# pihat.net
KiCad netlist of a schematic drawn in EAGLE
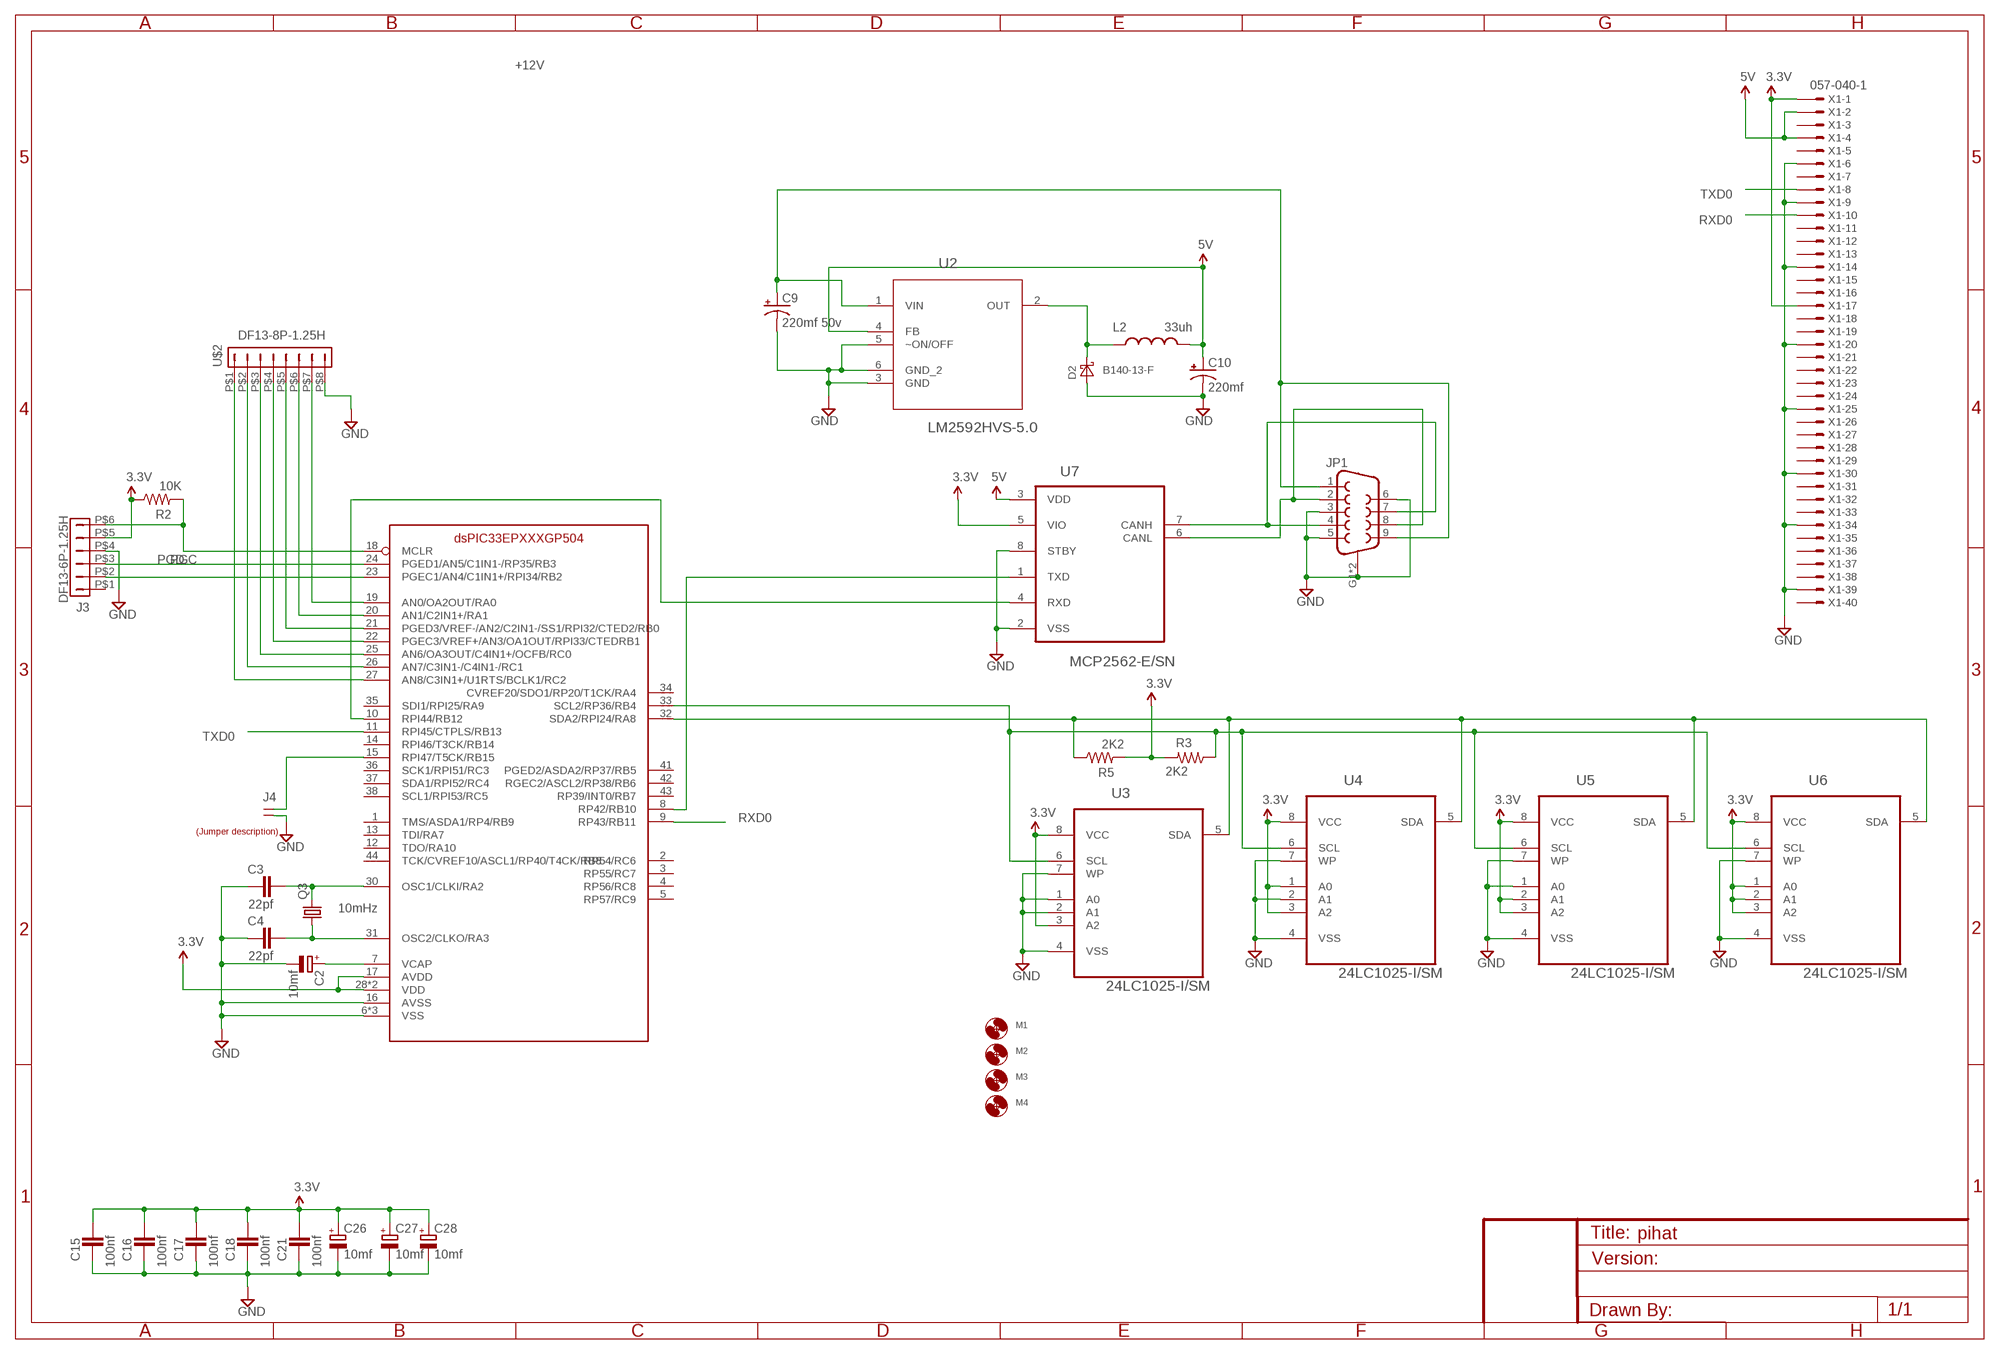
[diagram p0: schematic, sheet 1]

(export (version "E")
  (design (tool "Eeschema 10.0.6"))
  (components
    (comp (ref "C2")
      (value "10mf")
      (footprint "eagle-import:SMC_A")
      (fields (field (name "PARTNO") "T491A106K004AT"))
      (libsource (lib "eagle-import") (part "CAPACITOR_POL-SMC_A"))
    )
    (comp (ref "C3")
      (value "22pf")
      (footprint "eagle-import:C805")
      (fields (field (name "PARTNO") "C0805C220J5GACTU"))
      (libsource (lib "eagle-import") (part "CAPACITOR_NPOL-0805"))
    )
    (comp (ref "C4")
      (value "22pf")
      (footprint "eagle-import:C805")
      (fields (field (name "PARTNO") "C0805C220J5GACTU"))
      (libsource (lib "eagle-import") (part "CAPACITOR_NPOL-0805"))
    )
    (comp (ref "C9")
      (value "220mf 50v")
      (footprint "eagle-import:EIA7343")
      (fields (field (name "PARTNO") "T545X227M016ATE035"))
      (libsource (lib "eagle-import") (part "CAP_POL7343"))
    )
    (comp (ref "C10")
      (value "220mf")
      (footprint "eagle-import:EIA7343")
      (fields (field (name "PARTNO") "T545X227M016ATE035"))
      (libsource (lib "eagle-import") (part "CAP_POL7343"))
    )
    (comp (ref "C15")
      (value "100nf")
      (footprint "eagle-import:C805")
      (fields (field (name "PARTNO") "CL21F104ZBCNNNC"))
      (libsource (lib "eagle-import") (part "CAPACITOR_NPOL-0805"))
    )
    (comp (ref "C16")
      (value "100nf")
      (footprint "eagle-import:C805")
      (fields (field (name "PARTNO") "CL21F104ZBCNNNC"))
      (libsource (lib "eagle-import") (part "CAPACITOR_NPOL-0805"))
    )
    (comp (ref "C17")
      (value "100nf")
      (footprint "eagle-import:C805")
      (fields (field (name "PARTNO") "CL21F104ZBCNNNC"))
      (libsource (lib "eagle-import") (part "CAPACITOR_NPOL-0805"))
    )
    (comp (ref "C18")
      (value "100nf")
      (footprint "eagle-import:C805")
      (fields (field (name "PARTNO") "CL21F104ZBCNNNC"))
      (libsource (lib "eagle-import") (part "CAPACITOR_NPOL-0805"))
    )
    (comp (ref "C21")
      (value "100nf")
      (footprint "eagle-import:C805")
      (fields (field (name "PARTNO") "CL21F104ZBCNNNC"))
      (libsource (lib "eagle-import") (part "CAPACITOR_NPOL-0805"))
    )
    (comp (ref "C26")
      (value "10mf")
      (footprint "eagle-import:SMC_A")
      (fields (field (name "PARTNO") "T491A106K004AT"))
      (libsource (lib "eagle-import") (part "CAPACITOR_POL-SMC_A"))
    )
    (comp (ref "C27")
      (value "10mf")
      (footprint "eagle-import:SMC_A")
      (fields (field (name "PARTNO") "T491A106K004AT"))
      (libsource (lib "eagle-import") (part "CAPACITOR_POL-SMC_A"))
    )
    (comp (ref "C28")
      (value "10mf")
      (footprint "eagle-import:SMC_A")
      (fields (field (name "PARTNO") "T491A106K004AT"))
      (libsource (lib "eagle-import") (part "CAPACITOR_POL-SMC_A"))
    )
    (comp (ref "D2")
      (value "B140-13-F")
      (footprint "eagle-import:SMA")
      (libsource (lib "eagle-import") (part "DIODE-SCHOTTKY-SMA"))
    )
    (comp (ref "J3")
      (value "DF13-6P-1.25H")
      (footprint "eagle-import:DF13A-6P-1.25H")
      (fields (field (name "PARTNO") "DF13A-6P-1.25H(20)"))
      (libsource (lib "eagle-import") (part "DF13-6P-1.25H"))
    )
    (comp (ref "J4")
      (value "JUMPER-1X2")
      (footprint "eagle-import:JUMPER-1X2")
      (fields (field (name "PARTNO") "M20-9770246"))
      (libsource (lib "eagle-import") (part "JUMPER-1X2"))
    )
    (comp (ref "JP1")
      (value "DB9MALE")
      (footprint "eagle-import:DB9_MALE")
      (fields (field (name "PARTNO") "5747840-3"))
      (libsource (lib "eagle-import") (part "DB9MALE"))
    )
    (comp (ref "L2")
      (value "33uh")
      (footprint "eagle-import:1812")
      (fields (field (name "PARTNO") "B78108S1333K"))
      (libsource (lib "eagle-import") (part "INDUCTOR"))
    )
    (comp (ref "M1")
      (value "MOUNT-HOLE2.8")
      (footprint "eagle-import:2,8")
      (libsource (lib "eagle-import") (part "MOUNT-HOLE2.8"))
    )
    (comp (ref "M2")
      (value "MOUNT-HOLE2.8")
      (footprint "eagle-import:2,8")
      (libsource (lib "eagle-import") (part "MOUNT-HOLE2.8"))
    )
    (comp (ref "M3")
      (value "MOUNT-HOLE2.8")
      (footprint "eagle-import:2,8")
      (libsource (lib "eagle-import") (part "MOUNT-HOLE2.8"))
    )
    (comp (ref "M4")
      (value "MOUNT-HOLE2.8")
      (footprint "eagle-import:2,8")
      (libsource (lib "eagle-import") (part "MOUNT-HOLE2.8"))
    )
    (comp (ref "Q3")
      (value "10mHz")
      (footprint "eagle-import:HC49_S")
      (fields (field (name "PARTNO") "ATS100B-E"))
      (libsource (lib "eagle-import") (part "CRYSTALHC49S"))
    )
    (comp (ref "R2")
      (value "10K")
      (footprint "eagle-import:0603-RES")
      (fields (field (name "PARTNO") "RC0603FR-0710KL"))
      (libsource (lib "eagle-import") (part "RESISTOR0603-RES"))
    )
    (comp (ref "R3")
      (value "2K2")
      (footprint "eagle-import:0603-RES")
      (fields (field (name "PARTNO") "RC0603FR-072K2L"))
      (libsource (lib "eagle-import") (part "RESISTOR0603-RES"))
    )
    (comp (ref "R5")
      (value "2K2")
      (footprint "eagle-import:0603-RES")
      (fields (field (name "PARTNO") "RC0603FR-072K2L"))
      (libsource (lib "eagle-import") (part "RESISTOR0603-RES"))
    )
    (comp (ref "U$1")
      (value "LABEL_JUMPER_1X2")
      (footprint "eagle-import:JUMP2_DESC")
      (fields (field (name "OFF") "Normal") (field (name "ON") "Reset"))
      (libsource (lib "eagle-import") (part "LABEL_JUMPER_1X2"))
    )
    (comp (ref "U$2")
      (value "DF13-8P-1.25H")
      (footprint "eagle-import:DF13A-8P-1.25H")
      (fields (field (name "PARTNO") "DF13-8P-1.25H(50)"))
      (libsource (lib "eagle-import") (part "DF13-8P-1.25H"))
    )
    (comp (ref "U1")
      (value "DSPIC33EPXXXGP504")
      (footprint "eagle-import:TQFP44")
      (fields (field (name "PARTNO") "DSPIC33EP512GP504-I/PT"))
      (libsource (lib "eagle-import") (part "DSPIC33EPXXXGP504"))
    )
    (comp (ref "U2")
      (value "LM2592HVS-5.0")
      (footprint "eagle-import:TO170P1435X457-5N")
      (fields (field (name "PARTNO") "LM2592HVSX-5.0/NOPB"))
      (libsource (lib "eagle-import") (part "LM2592HVS-5.0"))
    )
    (comp (ref "U3")
      (value "24LC1025-I/SM")
      (footprint "eagle-import:SOIC8-N_MC")
      (fields (field (name "PARTNO") "24LC1025T-I/SN"))
      (libsource (lib "eagle-import") (part "24LC1025-I/SM"))
    )
    (comp (ref "U4")
      (value "24LC1025-I/SM")
      (footprint "eagle-import:SOIC8-N_MC")
      (fields (field (name "PARTNO") "24LC1025T-I/SN"))
      (libsource (lib "eagle-import") (part "24LC1025-I/SM"))
    )
    (comp (ref "U5")
      (value "24LC1025-I/SM")
      (footprint "eagle-import:SOIC8-N_MC")
      (fields (field (name "PARTNO") "24LC1025T-I/SN"))
      (libsource (lib "eagle-import") (part "24LC1025-I/SM"))
    )
    (comp (ref "U6")
      (value "24LC1025-I/SM")
      (footprint "eagle-import:SOIC8-N_MC")
      (fields (field (name "PARTNO") "24LC1025T-I/SN"))
      (libsource (lib "eagle-import") (part "24LC1025-I/SM"))
    )
    (comp (ref "U7")
      (value "MCP2562-E/SN")
      (footprint "eagle-import:SOIC-8N")
      (libsource (lib "eagle-import") (part "MCP2562-E/SN"))
    )
    (comp (ref "X1")
      (value "057-040-1")
      (footprint "eagle-import:057-040-1")
      (libsource (lib "eagle-import") (part "057-040-1"))
    )
  )
  (nets
    (net (code "1") (name "/+12V") (class "Default")
      (node (ref "C9") (pin "A") (pinfunction "+_A") (pintype "passive"))
      (node (ref "JP1") (pin "1") (pinfunction "1_1") (pintype "passive"))
      (node (ref "JP1") (pin "9") (pinfunction "9_9") (pintype "passive"))
      (node (ref "U2") (pin "1") (pinfunction "VIN_1") (pintype "power_in"))
    )
    (net (code "2") (name "/PGC") (class "Default")
      (node (ref "J3") (pin "P$2") (pinfunction "2_P$2") (pintype "passive"))
      (node (ref "U1") (pin "23") (pinfunction "PGEC1/AN4/C1IN1+/RPI34/RB2_23") (pintype "bidirectional"))
    )
    (net (code "3") (name "/PGD") (class "Default")
      (node (ref "J3") (pin "P$3") (pinfunction "3_P$3") (pintype "passive"))
      (node (ref "U1") (pin "24") (pinfunction "PGED1/AN5/C1IN1-/RP35/RB3_24") (pintype "bidirectional"))
    )
    (net (code "4") (name "/RXD0") (class "Default")
      (node (ref "U1") (pin "9") (pinfunction "RP43/RB11_9") (pintype "bidirectional"))
      (node (ref "X1") (pin "10") (pinfunction "S_10") (pintype "passive"))
    )
    (net (code "5") (name "/TXD0") (class "Default")
      (node (ref "U1") (pin "11") (pinfunction "RPI45/CTPLS/RB13_11") (pintype "bidirectional"))
      (node (ref "X1") (pin "8") (pinfunction "S_8") (pintype "passive"))
    )
    (net (code "6") (name "3.3V") (class "Default")
      (node (ref "C15") (pin "1") (pinfunction "1_1") (pintype "passive"))
      (node (ref "C16") (pin "1") (pinfunction "1_1") (pintype "passive"))
      (node (ref "C17") (pin "1") (pinfunction "1_1") (pintype "passive"))
      (node (ref "C18") (pin "1") (pinfunction "1_1") (pintype "passive"))
      (node (ref "C21") (pin "1") (pinfunction "1_1") (pintype "passive"))
      (node (ref "C26") (pin "+") (pinfunction "+_+") (pintype "passive"))
      (node (ref "C27") (pin "+") (pinfunction "+_+") (pintype "passive"))
      (node (ref "C28") (pin "+") (pinfunction "+_+") (pintype "passive"))
      (node (ref "J3") (pin "P$5") (pinfunction "5_P$5") (pintype "passive"))
      (node (ref "R2") (pin "1") (pinfunction "1_1") (pintype "passive"))
      (node (ref "R3") (pin "2") (pinfunction "2_2") (pintype "passive"))
      (node (ref "R5") (pin "2") (pinfunction "2_2") (pintype "passive"))
      (node (ref "U1") (pin "17") (pinfunction "AVDD_17") (pintype "bidirectional"))
      (node (ref "U1") (pin "28") (pinfunction "VDD_28") (pintype "bidirectional"))
      (node (ref "U1") (pin "40") (pinfunction "VDD_40") (pintype "bidirectional"))
      (node (ref "U3") (pin "3") (pinfunction "A2_3") (pintype "input"))
      (node (ref "U3") (pin "8") (pinfunction "VCC_8") (pintype "power_in"))
      (node (ref "U4") (pin "1") (pinfunction "A0_1") (pintype "input"))
      (node (ref "U4") (pin "3") (pinfunction "A2_3") (pintype "input"))
      (node (ref "U4") (pin "8") (pinfunction "VCC_8") (pintype "power_in"))
      (node (ref "U5") (pin "2") (pinfunction "A1_2") (pintype "input"))
      (node (ref "U5") (pin "3") (pinfunction "A2_3") (pintype "input"))
      (node (ref "U5") (pin "8") (pinfunction "VCC_8") (pintype "power_in"))
      (node (ref "U6") (pin "1") (pinfunction "A0_1") (pintype "input"))
      (node (ref "U6") (pin "2") (pinfunction "A1_2") (pintype "input"))
      (node (ref "U6") (pin "3") (pinfunction "A2_3") (pintype "input"))
      (node (ref "U6") (pin "8") (pinfunction "VCC_8") (pintype "power_in"))
      (node (ref "U7") (pin "5") (pinfunction "VIO_5") (pintype "power_in"))
      (node (ref "X1") (pin "1") (pinfunction "S_1") (pintype "passive"))
      (node (ref "X1") (pin "17") (pinfunction "S_17") (pintype "passive"))
    )
    (net (code "7") (name "5V") (class "Default")
      (node (ref "C10") (pin "A") (pinfunction "+_A") (pintype "passive"))
      (node (ref "L2") (pin "2") (pinfunction "2_2") (pintype "passive"))
      (node (ref "U2") (pin "4") (pinfunction "FB_4") (pintype "input"))
      (node (ref "U7") (pin "3") (pinfunction "VDD_3") (pintype "power_in"))
      (node (ref "X1") (pin "2") (pinfunction "S_2") (pintype "passive"))
      (node (ref "X1") (pin "4") (pinfunction "S_4") (pintype "passive"))
    )
    (net (code "8") (name "GND") (class "Default")
      (node (ref "C10") (pin "C") (pinfunction "-_C") (pintype "passive"))
      (node (ref "C15") (pin "2") (pinfunction "2_2") (pintype "passive"))
      (node (ref "C16") (pin "2") (pinfunction "2_2") (pintype "passive"))
      (node (ref "C17") (pin "2") (pinfunction "2_2") (pintype "passive"))
      (node (ref "C18") (pin "2") (pinfunction "2_2") (pintype "passive"))
      (node (ref "C2") (pin "-") (pinfunction "-_-") (pintype "passive"))
      (node (ref "C21") (pin "2") (pinfunction "2_2") (pintype "passive"))
      (node (ref "C26") (pin "-") (pinfunction "-_-") (pintype "passive"))
      (node (ref "C27") (pin "-") (pinfunction "-_-") (pintype "passive"))
      (node (ref "C28") (pin "-") (pinfunction "-_-") (pintype "passive"))
      (node (ref "C3") (pin "2") (pinfunction "2_2") (pintype "passive"))
      (node (ref "C4") (pin "2") (pinfunction "2_2") (pintype "passive"))
      (node (ref "C9") (pin "C") (pinfunction "-_C") (pintype "passive"))
      (node (ref "D2") (pin "A") (pinfunction "A_A") (pintype "passive"))
      (node (ref "J3") (pin "P$4") (pinfunction "4_P$4") (pintype "passive"))
      (node (ref "J4") (pin "2") (pinfunction "2_2") (pintype "bidirectional"))
      (node (ref "JP1") (pin "3") (pinfunction "3_3") (pintype "passive"))
      (node (ref "JP1") (pin "5") (pinfunction "5_5") (pintype "passive"))
      (node (ref "JP1") (pin "6") (pinfunction "6_6") (pintype "passive"))
      (node (ref "JP1") (pin "G1") (pinfunction "SHIELD_G1") (pintype "power_in"))
      (node (ref "JP1") (pin "G2") (pinfunction "SHIELD_G2") (pintype "power_in"))
      (node (ref "U$2") (pin "P$8") (pinfunction "8_P$8") (pintype "passive"))
      (node (ref "U1") (pin "16") (pinfunction "AVSS_16") (pintype "bidirectional"))
      (node (ref "U1") (pin "29") (pinfunction "VSS_29") (pintype "bidirectional"))
      (node (ref "U1") (pin "39") (pinfunction "VSS_39") (pintype "bidirectional"))
      (node (ref "U1") (pin "6") (pinfunction "VSS_6") (pintype "bidirectional"))
      (node (ref "U2") (pin "3") (pinfunction "GND_3") (pintype "passive"))
      (node (ref "U2") (pin "5") (pinfunction "~{ON/OFF}_5") (pintype "input"))
      (node (ref "U2") (pin "6") (pinfunction "GND_2_6") (pintype "passive"))
      (node (ref "U3") (pin "1") (pinfunction "A0_1") (pintype "input"))
      (node (ref "U3") (pin "2") (pinfunction "A1_2") (pintype "input"))
      (node (ref "U3") (pin "4") (pinfunction "VSS_4") (pintype "passive"))
      (node (ref "U3") (pin "7") (pinfunction "WP_7") (pintype "input"))
      (node (ref "U4") (pin "2") (pinfunction "A1_2") (pintype "input"))
      (node (ref "U4") (pin "4") (pinfunction "VSS_4") (pintype "passive"))
      (node (ref "U4") (pin "7") (pinfunction "WP_7") (pintype "input"))
      (node (ref "U5") (pin "1") (pinfunction "A0_1") (pintype "input"))
      (node (ref "U5") (pin "4") (pinfunction "VSS_4") (pintype "passive"))
      (node (ref "U5") (pin "7") (pinfunction "WP_7") (pintype "input"))
      (node (ref "U6") (pin "4") (pinfunction "VSS_4") (pintype "passive"))
      (node (ref "U6") (pin "7") (pinfunction "WP_7") (pintype "input"))
      (node (ref "U7") (pin "2") (pinfunction "VSS_2") (pintype "power_in"))
      (node (ref "U7") (pin "8") (pinfunction "STBY_8") (pintype "input"))
      (node (ref "X1") (pin "14") (pinfunction "S_14") (pintype "passive"))
      (node (ref "X1") (pin "20") (pinfunction "S_20") (pintype "passive"))
      (node (ref "X1") (pin "25") (pinfunction "S_25") (pintype "passive"))
      (node (ref "X1") (pin "30") (pinfunction "S_30") (pintype "passive"))
      (node (ref "X1") (pin "34") (pinfunction "S_34") (pintype "passive"))
      (node (ref "X1") (pin "39") (pinfunction "S_39") (pintype "passive"))
      (node (ref "X1") (pin "6") (pinfunction "S_6") (pintype "passive"))
      (node (ref "X1") (pin "9") (pinfunction "S_9") (pintype "passive"))
    )
    (net (code "9") (name "Net-(J3-6)") (class "Default")
      (node (ref "J3") (pin "P$6") (pinfunction "6_P$6") (pintype "passive"))
      (node (ref "R2") (pin "2") (pinfunction "2_2") (pintype "passive"))
      (node (ref "U1") (pin "18") (pinfunction "MCLR_18") (pintype "input"))
    )
    (net (code "10") (name "Net-(U$2-1)") (class "Default")
      (node (ref "U$2") (pin "P$1") (pinfunction "1_P$1") (pintype "passive"))
      (node (ref "U1") (pin "27") (pinfunction "AN8/C3IN1+/U1RTS/BCLK1/RC2_27") (pintype "bidirectional"))
    )
    (net (code "11") (name "Net-(U$2-2)") (class "Default")
      (node (ref "U$2") (pin "P$2") (pinfunction "2_P$2") (pintype "passive"))
      (node (ref "U1") (pin "26") (pinfunction "AN7/C3IN1-/C4IN1-/RC1_26") (pintype "bidirectional"))
    )
    (net (code "12") (name "Net-(U$2-3)") (class "Default")
      (node (ref "U$2") (pin "P$3") (pinfunction "3_P$3") (pintype "passive"))
      (node (ref "U1") (pin "25") (pinfunction "AN6/OA3OUT/C4IN1+/OCFB/RC0_25") (pintype "bidirectional"))
    )
    (net (code "13") (name "Net-(U$2-4)") (class "Default")
      (node (ref "U$2") (pin "P$4") (pinfunction "4_P$4") (pintype "passive"))
      (node (ref "U1") (pin "22") (pinfunction "PGEC3/VREF+/AN3/OA1OUT/RPI33/CTEDRB1_22") (pintype "bidirectional"))
    )
    (net (code "14") (name "Net-(U$2-5)") (class "Default")
      (node (ref "U$2") (pin "P$5") (pinfunction "5_P$5") (pintype "passive"))
      (node (ref "U1") (pin "21") (pinfunction "PGED3/VREF-/AN2/C2IN1-/SS1/RPI32/CTED2/RB0_21") (pintype "bidirectional"))
    )
    (net (code "15") (name "Net-(U$2-6)") (class "Default")
      (node (ref "U$2") (pin "P$6") (pinfunction "6_P$6") (pintype "passive"))
      (node (ref "U1") (pin "20") (pinfunction "AN1/C2IN1+/RA1_20") (pintype "bidirectional"))
    )
    (net (code "16") (name "Net-(U$2-7)") (class "Default")
      (node (ref "U$2") (pin "P$7") (pinfunction "7_P$7") (pintype "passive"))
      (node (ref "U1") (pin "19") (pinfunction "AN0/OA2OUT/RA0_19") (pintype "bidirectional"))
    )
    (net (code "17") (name "Net-(U1-OSC1{slash}CLKI{slash}RA2)") (class "Default")
      (node (ref "C3") (pin "1") (pinfunction "1_1") (pintype "passive"))
      (node (ref "Q3") (pin "2") (pinfunction "2_2") (pintype "passive"))
      (node (ref "U1") (pin "30") (pinfunction "OSC1/CLKI/RA2_30") (pintype "bidirectional"))
    )
    (net (code "18") (name "Net-(U1-OSC2{slash}CLKO{slash}RA3)") (class "Default")
      (node (ref "C4") (pin "1") (pinfunction "1_1") (pintype "passive"))
      (node (ref "Q3") (pin "1") (pinfunction "1_1") (pintype "passive"))
      (node (ref "U1") (pin "31") (pinfunction "OSC2/CLKO/RA3_31") (pintype "bidirectional"))
    )
    (net (code "19") (name "Net-(U1-RP42{slash}RB10)") (class "Default")
      (node (ref "U1") (pin "8") (pinfunction "RP42/RB10_8") (pintype "bidirectional"))
      (node (ref "U7") (pin "1") (pinfunction "TXD_1") (pintype "input"))
    )
    (net (code "20") (name "Net-(U1-RPI44{slash}RB12)") (class "Default")
      (node (ref "U1") (pin "10") (pinfunction "RPI44/RB12_10") (pintype "bidirectional"))
      (node (ref "U7") (pin "4") (pinfunction "RXD_4") (pintype "output"))
    )
    (net (code "21") (name "Net-(U1-RPI47{slash}T5CK{slash}RB15)") (class "Default")
      (node (ref "J4") (pin "1") (pinfunction "1_1") (pintype "bidirectional"))
      (node (ref "U1") (pin "15") (pinfunction "RPI47/T5CK/RB15_15") (pintype "bidirectional"))
    )
    (net (code "22") (name "Net-(U1-SCL2{slash}RP36{slash}RB4)") (class "Default")
      (node (ref "R3") (pin "1") (pinfunction "1_1") (pintype "passive"))
      (node (ref "U1") (pin "33") (pinfunction "SCL2/RP36/RB4_33") (pintype "bidirectional"))
      (node (ref "U3") (pin "6") (pinfunction "SCL_6") (pintype "input"))
      (node (ref "U4") (pin "6") (pinfunction "SCL_6") (pintype "input"))
      (node (ref "U5") (pin "6") (pinfunction "SCL_6") (pintype "input"))
      (node (ref "U6") (pin "6") (pinfunction "SCL_6") (pintype "input"))
    )
    (net (code "23") (name "Net-(U1-SDA2{slash}RPI24{slash}RA8)") (class "Default")
      (node (ref "R5") (pin "1") (pinfunction "1_1") (pintype "passive"))
      (node (ref "U1") (pin "32") (pinfunction "SDA2/RPI24/RA8_32") (pintype "bidirectional"))
      (node (ref "U3") (pin "5") (pinfunction "SDA_5") (pintype "bidirectional"))
      (node (ref "U4") (pin "5") (pinfunction "SDA_5") (pintype "bidirectional"))
      (node (ref "U5") (pin "5") (pinfunction "SDA_5") (pintype "bidirectional"))
      (node (ref "U6") (pin "5") (pinfunction "SDA_5") (pintype "bidirectional"))
    )
    (net (code "24") (name "Net-(U1-VCAP)") (class "Default")
      (node (ref "C2") (pin "+") (pinfunction "+_+") (pintype "passive"))
      (node (ref "U1") (pin "7") (pinfunction "VCAP_7") (pintype "bidirectional"))
    )
    (net (code "25") (name "Net-(U2-OUT)") (class "Default")
      (node (ref "D2") (pin "C") (pinfunction "C_C") (pintype "passive"))
      (node (ref "L2") (pin "1") (pinfunction "1_1") (pintype "passive"))
      (node (ref "U2") (pin "2") (pinfunction "OUT_2") (pintype "output"))
    )
    (net (code "26") (name "Net-(U7-CANH)") (class "Default")
      (node (ref "JP1") (pin "4") (pinfunction "4_4") (pintype "passive"))
      (node (ref "JP1") (pin "7") (pinfunction "7_7") (pintype "passive"))
      (node (ref "U7") (pin "7") (pinfunction "CANH_7") (pintype "bidirectional"))
    )
    (net (code "27") (name "Net-(U7-CANL)") (class "Default")
      (node (ref "JP1") (pin "2") (pinfunction "2_2") (pintype "passive"))
      (node (ref "JP1") (pin "8") (pinfunction "8_8") (pintype "passive"))
      (node (ref "U7") (pin "6") (pinfunction "CANL_6") (pintype "bidirectional"))
    )
    (net (code "28") (name "unconnected-(J3-1-PadP$1)") (class "Default")
      (node (ref "J3") (pin "P$1") (pinfunction "1_P$1") (pintype "passive"))
    )
    (net (code "29") (name "unconnected-(U1-CVREF20{slash}SDO1{slash}RP20{slash}T1CK{slash}RA4-Pad34)") (class "Default")
      (node (ref "U1") (pin "34") (pinfunction "CVREF20/SDO1/RP20/T1CK/RA4_34") (pintype "bidirectional"))
    )
    (net (code "30") (name "unconnected-(U1-PGED2{slash}ASDA2{slash}RP37{slash}RB5-Pad41)") (class "Default")
      (node (ref "U1") (pin "41") (pinfunction "PGED2/ASDA2/RP37/RB5_41") (pintype "bidirectional"))
    )
    (net (code "31") (name "unconnected-(U1-RGEC2{slash}ASCL2{slash}RP38{slash}RB6-Pad42)") (class "Default")
      (node (ref "U1") (pin "42") (pinfunction "RGEC2/ASCL2/RP38/RB6_42") (pintype "bidirectional"))
    )
    (net (code "32") (name "unconnected-(U1-RP39{slash}INT0{slash}RB7-Pad43)") (class "Default")
      (node (ref "U1") (pin "43") (pinfunction "RP39/INT0/RB7_43") (pintype "bidirectional"))
    )
    (net (code "33") (name "unconnected-(U1-RP54{slash}RC6-Pad2)") (class "Default")
      (node (ref "U1") (pin "2") (pinfunction "RP54/RC6_2") (pintype "bidirectional"))
    )
    (net (code "34") (name "unconnected-(U1-RP55{slash}RC7-Pad3)") (class "Default")
      (node (ref "U1") (pin "3") (pinfunction "RP55/RC7_3") (pintype "bidirectional"))
    )
    (net (code "35") (name "unconnected-(U1-RP56{slash}RC8-Pad4)") (class "Default")
      (node (ref "U1") (pin "4") (pinfunction "RP56/RC8_4") (pintype "bidirectional"))
    )
    (net (code "36") (name "unconnected-(U1-RP57{slash}RC9-Pad5)") (class "Default")
      (node (ref "U1") (pin "5") (pinfunction "RP57/RC9_5") (pintype "bidirectional"))
    )
    (net (code "37") (name "unconnected-(U1-RPI46{slash}T3CK{slash}RB14-Pad14)") (class "Default")
      (node (ref "U1") (pin "14") (pinfunction "RPI46/T3CK/RB14_14") (pintype "bidirectional"))
    )
    (net (code "38") (name "unconnected-(U1-SCK1{slash}RPI51{slash}RC3-Pad36)") (class "Default")
      (node (ref "U1") (pin "36") (pinfunction "SCK1/RPI51/RC3_36") (pintype "bidirectional"))
    )
    (net (code "39") (name "unconnected-(U1-SCL1{slash}RPI53{slash}RC5-Pad38)") (class "Default")
      (node (ref "U1") (pin "38") (pinfunction "SCL1/RPI53/RC5_38") (pintype "bidirectional"))
    )
    (net (code "40") (name "unconnected-(U1-SDA1{slash}RPI52{slash}RC4-Pad37)") (class "Default")
      (node (ref "U1") (pin "37") (pinfunction "SDA1/RPI52/RC4_37") (pintype "bidirectional"))
    )
    (net (code "41") (name "unconnected-(U1-SDI1{slash}RPI25{slash}RA9-Pad35)") (class "Default")
      (node (ref "U1") (pin "35") (pinfunction "SDI1/RPI25/RA9_35") (pintype "bidirectional"))
    )
    (net (code "42") (name "unconnected-(U1-TCK{slash}CVREF10{slash}ASCL1{slash}RP40{slash}T4CK{slash}RB8-Pad44)") (class "Default")
      (node (ref "U1") (pin "44") (pinfunction "TCK/CVREF10/ASCL1/RP40/T4CK/RB8_44") (pintype "bidirectional"))
    )
    (net (code "43") (name "unconnected-(U1-TDI{slash}RA7-Pad13)") (class "Default")
      (node (ref "U1") (pin "13") (pinfunction "TDI/RA7_13") (pintype "bidirectional"))
    )
    (net (code "44") (name "unconnected-(U1-TDO{slash}RA10-Pad12)") (class "Default")
      (node (ref "U1") (pin "12") (pinfunction "TDO/RA10_12") (pintype "bidirectional"))
    )
    (net (code "45") (name "unconnected-(U1-TMS{slash}ASDA1{slash}RP4{slash}RB9-Pad1)") (class "Default")
      (node (ref "U1") (pin "1") (pinfunction "TMS/ASDA1/RP4/RB9_1") (pintype "bidirectional"))
    )
    (net (code "46") (name "unconnected-(X1AA-S-Pad33)") (class "Default")
      (node (ref "X1") (pin "33") (pinfunction "S_33") (pintype "passive"))
    )
    (net (code "47") (name "unconnected-(X1AC-S-Pad35)") (class "Default")
      (node (ref "X1") (pin "35") (pinfunction "S_35") (pintype "passive"))
    )
    (net (code "48") (name "unconnected-(X1AD-S-Pad36)") (class "Default")
      (node (ref "X1") (pin "36") (pinfunction "S_36") (pintype "passive"))
    )
    (net (code "49") (name "unconnected-(X1AE-S-Pad37)") (class "Default")
      (node (ref "X1") (pin "37") (pinfunction "S_37") (pintype "passive"))
    )
    (net (code "50") (name "unconnected-(X1AF-S-Pad38)") (class "Default")
      (node (ref "X1") (pin "38") (pinfunction "S_38") (pintype "passive"))
    )
    (net (code "51") (name "unconnected-(X1AI-S-Pad40)") (class "Default")
      (node (ref "X1") (pin "40") (pinfunction "S_40") (pintype "passive"))
    )
    (net (code "52") (name "unconnected-(X1AJ-S-Pad5)") (class "Default")
      (node (ref "X1") (pin "5") (pinfunction "S_5") (pintype "passive"))
    )
    (net (code "53") (name "unconnected-(X1AL-S-Pad7)") (class "Default")
      (node (ref "X1") (pin "7") (pinfunction "S_7") (pintype "passive"))
    )
    (net (code "54") (name "unconnected-(X1C-S-Pad11)") (class "Default")
      (node (ref "X1") (pin "11") (pinfunction "S_11") (pintype "passive"))
    )
    (net (code "55") (name "unconnected-(X1D-S-Pad12)") (class "Default")
      (node (ref "X1") (pin "12") (pinfunction "S_12") (pintype "passive"))
    )
    (net (code "56") (name "unconnected-(X1E-S-Pad13)") (class "Default")
      (node (ref "X1") (pin "13") (pinfunction "S_13") (pintype "passive"))
    )
    (net (code "57") (name "unconnected-(X1G-S-Pad15)") (class "Default")
      (node (ref "X1") (pin "15") (pinfunction "S_15") (pintype "passive"))
    )
    (net (code "58") (name "unconnected-(X1H-S-Pad16)") (class "Default")
      (node (ref "X1") (pin "16") (pinfunction "S_16") (pintype "passive"))
    )
    (net (code "59") (name "unconnected-(X1J-S-Pad18)") (class "Default")
      (node (ref "X1") (pin "18") (pinfunction "S_18") (pintype "passive"))
    )
    (net (code "60") (name "unconnected-(X1K-S-Pad19)") (class "Default")
      (node (ref "X1") (pin "19") (pinfunction "S_19") (pintype "passive"))
    )
    (net (code "61") (name "unconnected-(X1N-S-Pad21)") (class "Default")
      (node (ref "X1") (pin "21") (pinfunction "S_21") (pintype "passive"))
    )
    (net (code "62") (name "unconnected-(X1O-S-Pad22)") (class "Default")
      (node (ref "X1") (pin "22") (pinfunction "S_22") (pintype "passive"))
    )
    (net (code "63") (name "unconnected-(X1P-S-Pad23)") (class "Default")
      (node (ref "X1") (pin "23") (pinfunction "S_23") (pintype "passive"))
    )
    (net (code "64") (name "unconnected-(X1Q-S-Pad24)") (class "Default")
      (node (ref "X1") (pin "24") (pinfunction "S_24") (pintype "passive"))
    )
    (net (code "65") (name "unconnected-(X1S-S-Pad26)") (class "Default")
      (node (ref "X1") (pin "26") (pinfunction "S_26") (pintype "passive"))
    )
    (net (code "66") (name "unconnected-(X1T-S-Pad27)") (class "Default")
      (node (ref "X1") (pin "27") (pinfunction "S_27") (pintype "passive"))
    )
    (net (code "67") (name "unconnected-(X1U-S-Pad28)") (class "Default")
      (node (ref "X1") (pin "28") (pinfunction "S_28") (pintype "passive"))
    )
    (net (code "68") (name "unconnected-(X1V-S-Pad29)") (class "Default")
      (node (ref "X1") (pin "29") (pinfunction "S_29") (pintype "passive"))
    )
    (net (code "69") (name "unconnected-(X1W-S-Pad3)") (class "Default")
      (node (ref "X1") (pin "3") (pinfunction "S_3") (pintype "passive"))
    )
    (net (code "70") (name "unconnected-(X1Y-S-Pad31)") (class "Default")
      (node (ref "X1") (pin "31") (pinfunction "S_31") (pintype "passive"))
    )
    (net (code "71") (name "unconnected-(X1Z-S-Pad32)") (class "Default")
      (node (ref "X1") (pin "32") (pinfunction "S_32") (pintype "passive"))
    )
  )
)
